# sunclock_back.net
KiCad netlist of a schematic drawn in EAGLE
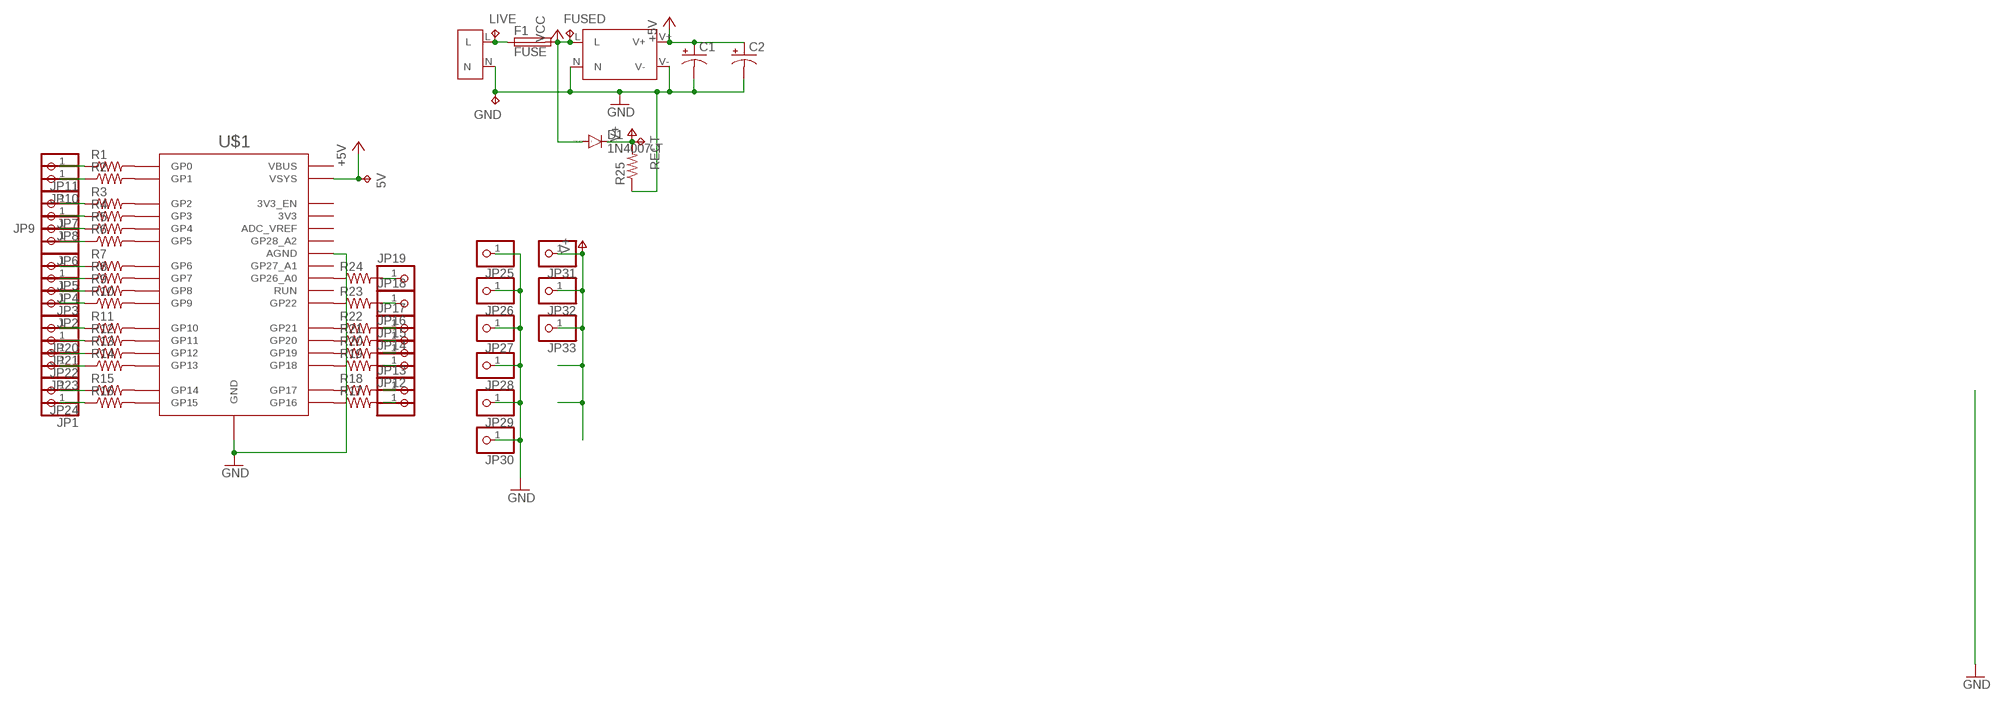
[diagram p0: schematic, sheet 1]

(export (version "E")
  (design (tool "Eeschema 10.0.6"))
  (components
    (comp (ref "5V")
      (value "TPB2,54")
      (footprint "eagle-import:B2,54")
      (libsource (lib "eagle-import") (part "TPB2,54"))
    )
    (comp (ref "AC1")
      (value "AC_IN")
      (footprint "eagle-import:AC_IN")
      (libsource (lib "eagle-import") (part "AC_IN"))
    )
    (comp (ref "C1")
      (value "CPOL-USE3.5-10")
      (footprint "eagle-import:E3,5-10")
      (libsource (lib "eagle-import") (part "CPOL-USE3.5-10"))
    )
    (comp (ref "C2")
      (value "CPOL-USE3.5-10")
      (footprint "eagle-import:E3,5-10")
      (libsource (lib "eagle-import") (part "CPOL-USE3.5-10"))
    )
    (comp (ref "D1")
      (value "1N4007-T")
      (footprint "eagle-import:DIOAD1140W86L463D236B")
      (libsource (lib "eagle-import") (part "1N4007-T"))
    )
    (comp (ref "F1")
      (value "FUSE")
      (footprint "eagle-import:FUSE")
      (libsource (lib "eagle-import") (part "FUSE"))
    )
    (comp (ref "FUSED")
      (value "TPB2,54")
      (footprint "eagle-import:B2,54")
      (libsource (lib "eagle-import") (part "TPB2,54"))
    )
    (comp (ref "GND")
      (value "TPB2,54")
      (footprint "eagle-import:B2,54")
      (libsource (lib "eagle-import") (part "TPB2,54"))
    )
    (comp (ref "JP1")
      (value "PINHD-1X1")
      (footprint "eagle-import:1X01")
      (libsource (lib "eagle-import") (part "PINHD-1X1"))
    )
    (comp (ref "JP2")
      (value "PINHD-1X1")
      (footprint "eagle-import:1X01")
      (libsource (lib "eagle-import") (part "PINHD-1X1"))
    )
    (comp (ref "JP3")
      (value "PINHD-1X1")
      (footprint "eagle-import:1X01")
      (libsource (lib "eagle-import") (part "PINHD-1X1"))
    )
    (comp (ref "JP4")
      (value "PINHD-1X1")
      (footprint "eagle-import:1X01")
      (libsource (lib "eagle-import") (part "PINHD-1X1"))
    )
    (comp (ref "JP5")
      (value "PINHD-1X1")
      (footprint "eagle-import:1X01")
      (libsource (lib "eagle-import") (part "PINHD-1X1"))
    )
    (comp (ref "JP6")
      (value "PINHD-1X1")
      (footprint "eagle-import:1X01")
      (libsource (lib "eagle-import") (part "PINHD-1X1"))
    )
    (comp (ref "JP7")
      (value "PINHD-1X1")
      (footprint "eagle-import:1X01")
      (libsource (lib "eagle-import") (part "PINHD-1X1"))
    )
    (comp (ref "JP8")
      (value "PINHD-1X1")
      (footprint "eagle-import:1X01")
      (libsource (lib "eagle-import") (part "PINHD-1X1"))
    )
    (comp (ref "JP9")
      (value "PINHD-1X1")
      (footprint "eagle-import:1X01")
      (libsource (lib "eagle-import") (part "PINHD-1X1"))
    )
    (comp (ref "JP10")
      (value "PINHD-1X1")
      (footprint "eagle-import:1X01")
      (libsource (lib "eagle-import") (part "PINHD-1X1"))
    )
    (comp (ref "JP11")
      (value "PINHD-1X1")
      (footprint "eagle-import:1X01")
      (libsource (lib "eagle-import") (part "PINHD-1X1"))
    )
    (comp (ref "JP12")
      (value "PINHD-1X1")
      (footprint "eagle-import:1X01")
      (libsource (lib "eagle-import") (part "PINHD-1X1"))
    )
    (comp (ref "JP13")
      (value "PINHD-1X1")
      (footprint "eagle-import:1X01")
      (libsource (lib "eagle-import") (part "PINHD-1X1"))
    )
    (comp (ref "JP14")
      (value "PINHD-1X1")
      (footprint "eagle-import:1X01")
      (libsource (lib "eagle-import") (part "PINHD-1X1"))
    )
    (comp (ref "JP15")
      (value "PINHD-1X1")
      (footprint "eagle-import:1X01")
      (libsource (lib "eagle-import") (part "PINHD-1X1"))
    )
    (comp (ref "JP16")
      (value "PINHD-1X1")
      (footprint "eagle-import:1X01")
      (libsource (lib "eagle-import") (part "PINHD-1X1"))
    )
    (comp (ref "JP17")
      (value "PINHD-1X1")
      (footprint "eagle-import:1X01")
      (libsource (lib "eagle-import") (part "PINHD-1X1"))
    )
    (comp (ref "JP18")
      (value "PINHD-1X1")
      (footprint "eagle-import:1X01")
      (libsource (lib "eagle-import") (part "PINHD-1X1"))
    )
    (comp (ref "JP19")
      (value "PINHD-1X1")
      (footprint "eagle-import:1X01")
      (libsource (lib "eagle-import") (part "PINHD-1X1"))
    )
    (comp (ref "JP20")
      (value "PINHD-1X1")
      (footprint "eagle-import:1X01")
      (libsource (lib "eagle-import") (part "PINHD-1X1"))
    )
    (comp (ref "JP21")
      (value "PINHD-1X1")
      (footprint "eagle-import:1X01")
      (libsource (lib "eagle-import") (part "PINHD-1X1"))
    )
    (comp (ref "JP22")
      (value "PINHD-1X1")
      (footprint "eagle-import:1X01")
      (libsource (lib "eagle-import") (part "PINHD-1X1"))
    )
    (comp (ref "JP23")
      (value "PINHD-1X1")
      (footprint "eagle-import:1X01")
      (libsource (lib "eagle-import") (part "PINHD-1X1"))
    )
    (comp (ref "JP24")
      (value "PINHD-1X1")
      (footprint "eagle-import:1X01")
      (libsource (lib "eagle-import") (part "PINHD-1X1"))
    )
    (comp (ref "JP25")
      (value "PINHD-1X1")
      (footprint "eagle-import:1X01")
      (libsource (lib "eagle-import") (part "PINHD-1X1"))
    )
    (comp (ref "JP26")
      (value "PINHD-1X1")
      (footprint "eagle-import:1X01")
      (libsource (lib "eagle-import") (part "PINHD-1X1"))
    )
    (comp (ref "JP27")
      (value "PINHD-1X1")
      (footprint "eagle-import:1X01")
      (libsource (lib "eagle-import") (part "PINHD-1X1"))
    )
    (comp (ref "JP28")
      (value "PINHD-1X1")
      (footprint "eagle-import:1X01")
      (libsource (lib "eagle-import") (part "PINHD-1X1"))
    )
    (comp (ref "JP29")
      (value "PINHD-1X1")
      (footprint "eagle-import:1X01")
      (libsource (lib "eagle-import") (part "PINHD-1X1"))
    )
    (comp (ref "JP30")
      (value "PINHD-1X1")
      (footprint "eagle-import:1X01")
      (libsource (lib "eagle-import") (part "PINHD-1X1"))
    )
    (comp (ref "JP31")
      (value "PINHD-1X1")
      (footprint "eagle-import:1X01")
      (libsource (lib "eagle-import") (part "PINHD-1X1"))
    )
    (comp (ref "JP32")
      (value "PINHD-1X1")
      (footprint "eagle-import:1X01")
      (libsource (lib "eagle-import") (part "PINHD-1X1"))
    )
    (comp (ref "JP33")
      (value "PINHD-1X1")
      (footprint "eagle-import:1X01")
      (libsource (lib "eagle-import") (part "PINHD-1X1"))
    )
    (comp (ref "LIVE")
      (value "TPB2,54")
      (footprint "eagle-import:B2,54")
      (libsource (lib "eagle-import") (part "TPB2,54"))
    )
    (comp (ref "P1")
      (value "ACDC")
      (footprint "eagle-import:ACDC")
      (libsource (lib "eagle-import") (part "ACDC"))
    )
    (comp (ref "R1")
      (value "R-US_0204/7")
      (footprint "eagle-import:0204_7")
      (libsource (lib "eagle-import") (part "R-US_0204/7"))
    )
    (comp (ref "R2")
      (value "R-US_0204/7")
      (footprint "eagle-import:0204_7")
      (libsource (lib "eagle-import") (part "R-US_0204/7"))
    )
    (comp (ref "R3")
      (value "R-US_0204/7")
      (footprint "eagle-import:0204_7")
      (libsource (lib "eagle-import") (part "R-US_0204/7"))
    )
    (comp (ref "R4")
      (value "R-US_0204/7")
      (footprint "eagle-import:0204_7")
      (libsource (lib "eagle-import") (part "R-US_0204/7"))
    )
    (comp (ref "R5")
      (value "R-US_0204/7")
      (footprint "eagle-import:0204_7")
      (libsource (lib "eagle-import") (part "R-US_0204/7"))
    )
    (comp (ref "R6")
      (value "R-US_0204/7")
      (footprint "eagle-import:0204_7")
      (libsource (lib "eagle-import") (part "R-US_0204/7"))
    )
    (comp (ref "R7")
      (value "R-US_0204/7")
      (footprint "eagle-import:0204_7")
      (libsource (lib "eagle-import") (part "R-US_0204/7"))
    )
    (comp (ref "R8")
      (value "R-US_0204/7")
      (footprint "eagle-import:0204_7")
      (libsource (lib "eagle-import") (part "R-US_0204/7"))
    )
    (comp (ref "R9")
      (value "R-US_0204/7")
      (footprint "eagle-import:0204_7")
      (libsource (lib "eagle-import") (part "R-US_0204/7"))
    )
    (comp (ref "R10")
      (value "R-US_0204/7")
      (footprint "eagle-import:0204_7")
      (libsource (lib "eagle-import") (part "R-US_0204/7"))
    )
    (comp (ref "R11")
      (value "R-US_0204/7")
      (footprint "eagle-import:0204_7")
      (libsource (lib "eagle-import") (part "R-US_0204/7"))
    )
    (comp (ref "R12")
      (value "R-US_0204/7")
      (footprint "eagle-import:0204_7")
      (libsource (lib "eagle-import") (part "R-US_0204/7"))
    )
    (comp (ref "R13")
      (value "R-US_0204/7")
      (footprint "eagle-import:0204_7")
      (libsource (lib "eagle-import") (part "R-US_0204/7"))
    )
    (comp (ref "R14")
      (value "R-US_0204/7")
      (footprint "eagle-import:0204_7")
      (libsource (lib "eagle-import") (part "R-US_0204/7"))
    )
    (comp (ref "R15")
      (value "R-US_0204/7")
      (footprint "eagle-import:0204_7")
      (libsource (lib "eagle-import") (part "R-US_0204/7"))
    )
    (comp (ref "R16")
      (value "R-US_0204/7")
      (footprint "eagle-import:0204_7")
      (libsource (lib "eagle-import") (part "R-US_0204/7"))
    )
    (comp (ref "R17")
      (value "R-US_0204/7")
      (footprint "eagle-import:0204_7")
      (libsource (lib "eagle-import") (part "R-US_0204/7"))
    )
    (comp (ref "R18")
      (value "R-US_0204/7")
      (footprint "eagle-import:0204_7")
      (libsource (lib "eagle-import") (part "R-US_0204/7"))
    )
    (comp (ref "R19")
      (value "R-US_0204/7")
      (footprint "eagle-import:0204_7")
      (libsource (lib "eagle-import") (part "R-US_0204/7"))
    )
    (comp (ref "R20")
      (value "R-US_0204/7")
      (footprint "eagle-import:0204_7")
      (libsource (lib "eagle-import") (part "R-US_0204/7"))
    )
    (comp (ref "R21")
      (value "R-US_0204/7")
      (footprint "eagle-import:0204_7")
      (libsource (lib "eagle-import") (part "R-US_0204/7"))
    )
    (comp (ref "R22")
      (value "R-US_0204/7")
      (footprint "eagle-import:0204_7")
      (libsource (lib "eagle-import") (part "R-US_0204/7"))
    )
    (comp (ref "R23")
      (value "R-US_0204/7")
      (footprint "eagle-import:0204_7")
      (libsource (lib "eagle-import") (part "R-US_0204/7"))
    )
    (comp (ref "R24")
      (value "R-US_0204/7")
      (footprint "eagle-import:0204_7")
      (libsource (lib "eagle-import") (part "R-US_0204/7"))
    )
    (comp (ref "R25")
      (value "R-US_0204/7")
      (footprint "eagle-import:0204_7")
      (libsource (lib "eagle-import") (part "R-US_0204/7"))
    )
    (comp (ref "RECT")
      (value "TPB2,54")
      (footprint "eagle-import:B2,54")
      (libsource (lib "eagle-import") (part "TPB2,54"))
    )
    (comp (ref "U$1")
      (value "RPI_PICO-TH")
      (footprint "eagle-import:RPI_PICO_TH")
      (libsource (lib "eagle-import") (part "RPI_PICO-TH"))
    )
  )
  (nets
    (net (code "1") (name "+5V") (class "Default")
      (node (ref "5V") (pin "TP") (pinfunction "TP_TP") (pintype "input"))
      (node (ref "C1") (pin "+") (pinfunction "+_+") (pintype "passive"))
      (node (ref "C2") (pin "+") (pinfunction "+_+") (pintype "passive"))
      (node (ref "P1") (pin "V+") (pinfunction "V+_V+") (pintype "bidirectional"))
      (node (ref "U$1") (pin "VSYS") (pinfunction "VSYS_VSYS") (pintype "bidirectional"))
    )
    (net (code "2") (name "GND") (class "Default")
      (node (ref "AC1") (pin "N") (pinfunction "N_N") (pintype "bidirectional"))
      (node (ref "C1") (pin "-") (pinfunction "-_-") (pintype "passive"))
      (node (ref "C2") (pin "-") (pinfunction "-_-") (pintype "passive"))
      (node (ref "GND") (pin "TP") (pinfunction "TP_TP") (pintype "input"))
      (node (ref "JP25") (pin "1") (pinfunction "1_1") (pintype "passive"))
      (node (ref "JP26") (pin "1") (pinfunction "1_1") (pintype "passive"))
      (node (ref "JP27") (pin "1") (pinfunction "1_1") (pintype "passive"))
      (node (ref "JP28") (pin "1") (pinfunction "1_1") (pintype "passive"))
      (node (ref "JP29") (pin "1") (pinfunction "1_1") (pintype "passive"))
      (node (ref "JP30") (pin "1") (pinfunction "1_1") (pintype "passive"))
      (node (ref "P1") (pin "N") (pinfunction "N_N") (pintype "bidirectional"))
      (node (ref "P1") (pin "V-") (pinfunction "V-_V-") (pintype "bidirectional"))
      (node (ref "R25") (pin "1") (pinfunction "1_1") (pintype "passive"))
      (node (ref "U$1") (pin "AGND") (pinfunction "AGND_AGND") (pintype "bidirectional"))
      (node (ref "U$1") (pin "GND@1") (pinfunction "GND_GND@1") (pintype "bidirectional"))
      (node (ref "U$1") (pin "GND@2") (pinfunction "GND_GND@2") (pintype "bidirectional"))
      (node (ref "U$1") (pin "GND@3") (pinfunction "GND_GND@3") (pintype "bidirectional"))
      (node (ref "U$1") (pin "GND@4") (pinfunction "GND_GND@4") (pintype "bidirectional"))
      (node (ref "U$1") (pin "GND@6") (pinfunction "GND_GND@6") (pintype "bidirectional"))
      (node (ref "U$1") (pin "GND@7") (pinfunction "GND_GND@7") (pintype "bidirectional"))
      (node (ref "U$1") (pin "GND@8") (pinfunction "GND_GND@8") (pintype "bidirectional"))
    )
    (net (code "3") (name "Net-(F1-1)") (class "Default")
      (node (ref "AC1") (pin "L") (pinfunction "L_L") (pintype "bidirectional"))
      (node (ref "F1") (pin "P$1") (pinfunction "1_P$1") (pintype "passive"))
      (node (ref "LIVE") (pin "TP") (pinfunction "TP_TP") (pintype "input"))
    )
    (net (code "4") (name "Net-(JP1-Pad1)") (class "Default")
      (node (ref "JP1") (pin "1") (pinfunction "1_1") (pintype "passive"))
      (node (ref "R16") (pin "1") (pinfunction "1_1") (pintype "passive"))
    )
    (net (code "5") (name "Net-(JP2-Pad1)") (class "Default")
      (node (ref "JP2") (pin "1") (pinfunction "1_1") (pintype "passive"))
      (node (ref "R10") (pin "1") (pinfunction "1_1") (pintype "passive"))
    )
    (net (code "6") (name "Net-(JP3-Pad1)") (class "Default")
      (node (ref "JP3") (pin "1") (pinfunction "1_1") (pintype "passive"))
      (node (ref "R9") (pin "1") (pinfunction "1_1") (pintype "passive"))
    )
    (net (code "7") (name "Net-(JP4-Pad1)") (class "Default")
      (node (ref "JP4") (pin "1") (pinfunction "1_1") (pintype "passive"))
      (node (ref "R8") (pin "1") (pinfunction "1_1") (pintype "passive"))
    )
    (net (code "8") (name "Net-(JP5-Pad1)") (class "Default")
      (node (ref "JP5") (pin "1") (pinfunction "1_1") (pintype "passive"))
      (node (ref "R7") (pin "1") (pinfunction "1_1") (pintype "passive"))
    )
    (net (code "9") (name "Net-(JP6-Pad1)") (class "Default")
      (node (ref "JP6") (pin "1") (pinfunction "1_1") (pintype "passive"))
      (node (ref "R6") (pin "1") (pinfunction "1_1") (pintype "passive"))
    )
    (net (code "10") (name "Net-(JP7-Pad1)") (class "Default")
      (node (ref "JP7") (pin "1") (pinfunction "1_1") (pintype "passive"))
      (node (ref "R3") (pin "1") (pinfunction "1_1") (pintype "passive"))
    )
    (net (code "11") (name "Net-(JP8-Pad1)") (class "Default")
      (node (ref "JP8") (pin "1") (pinfunction "1_1") (pintype "passive"))
      (node (ref "R4") (pin "1") (pinfunction "1_1") (pintype "passive"))
    )
    (net (code "12") (name "Net-(JP9-Pad1)") (class "Default")
      (node (ref "JP9") (pin "1") (pinfunction "1_1") (pintype "passive"))
      (node (ref "R5") (pin "1") (pinfunction "1_1") (pintype "passive"))
    )
    (net (code "13") (name "Net-(JP10-Pad1)") (class "Default")
      (node (ref "JP10") (pin "1") (pinfunction "1_1") (pintype "passive"))
      (node (ref "R2") (pin "1") (pinfunction "1_1") (pintype "passive"))
    )
    (net (code "14") (name "Net-(JP11-Pad1)") (class "Default")
      (node (ref "JP11") (pin "1") (pinfunction "1_1") (pintype "passive"))
      (node (ref "R1") (pin "1") (pinfunction "1_1") (pintype "passive"))
    )
    (net (code "15") (name "Net-(JP12-Pad1)") (class "Default")
      (node (ref "JP12") (pin "1") (pinfunction "1_1") (pintype "passive"))
      (node (ref "R17") (pin "2") (pinfunction "2_2") (pintype "passive"))
    )
    (net (code "16") (name "Net-(JP13-Pad1)") (class "Default")
      (node (ref "JP13") (pin "1") (pinfunction "1_1") (pintype "passive"))
      (node (ref "R18") (pin "2") (pinfunction "2_2") (pintype "passive"))
    )
    (net (code "17") (name "Net-(JP14-Pad1)") (class "Default")
      (node (ref "JP14") (pin "1") (pinfunction "1_1") (pintype "passive"))
      (node (ref "R19") (pin "2") (pinfunction "2_2") (pintype "passive"))
    )
    (net (code "18") (name "Net-(JP15-Pad1)") (class "Default")
      (node (ref "JP15") (pin "1") (pinfunction "1_1") (pintype "passive"))
      (node (ref "R20") (pin "2") (pinfunction "2_2") (pintype "passive"))
    )
    (net (code "19") (name "Net-(JP16-Pad1)") (class "Default")
      (node (ref "JP16") (pin "1") (pinfunction "1_1") (pintype "passive"))
      (node (ref "R21") (pin "2") (pinfunction "2_2") (pintype "passive"))
    )
    (net (code "20") (name "Net-(JP17-Pad1)") (class "Default")
      (node (ref "JP17") (pin "1") (pinfunction "1_1") (pintype "passive"))
      (node (ref "R22") (pin "2") (pinfunction "2_2") (pintype "passive"))
    )
    (net (code "21") (name "Net-(JP18-Pad1)") (class "Default")
      (node (ref "JP18") (pin "1") (pinfunction "1_1") (pintype "passive"))
      (node (ref "R23") (pin "2") (pinfunction "2_2") (pintype "passive"))
    )
    (net (code "22") (name "Net-(JP19-Pad1)") (class "Default")
      (node (ref "JP19") (pin "1") (pinfunction "1_1") (pintype "passive"))
      (node (ref "R24") (pin "2") (pinfunction "2_2") (pintype "passive"))
    )
    (net (code "23") (name "Net-(JP20-Pad1)") (class "Default")
      (node (ref "JP20") (pin "1") (pinfunction "1_1") (pintype "passive"))
      (node (ref "R11") (pin "1") (pinfunction "1_1") (pintype "passive"))
    )
    (net (code "24") (name "Net-(JP21-Pad1)") (class "Default")
      (node (ref "JP21") (pin "1") (pinfunction "1_1") (pintype "passive"))
      (node (ref "R12") (pin "1") (pinfunction "1_1") (pintype "passive"))
    )
    (net (code "25") (name "Net-(JP22-Pad1)") (class "Default")
      (node (ref "JP22") (pin "1") (pinfunction "1_1") (pintype "passive"))
      (node (ref "R13") (pin "1") (pinfunction "1_1") (pintype "passive"))
    )
    (net (code "26") (name "Net-(JP23-Pad1)") (class "Default")
      (node (ref "JP23") (pin "1") (pinfunction "1_1") (pintype "passive"))
      (node (ref "R14") (pin "1") (pinfunction "1_1") (pintype "passive"))
    )
    (net (code "27") (name "Net-(JP24-Pad1)") (class "Default")
      (node (ref "JP24") (pin "1") (pinfunction "1_1") (pintype "passive"))
      (node (ref "R15") (pin "1") (pinfunction "1_1") (pintype "passive"))
    )
    (net (code "28") (name "Net-(R1-Pad2)") (class "Default")
      (node (ref "R1") (pin "2") (pinfunction "2_2") (pintype "passive"))
      (node (ref "U$1") (pin "GP0") (pinfunction "GP0_GP0") (pintype "bidirectional"))
    )
    (net (code "29") (name "Net-(R2-Pad2)") (class "Default")
      (node (ref "R2") (pin "2") (pinfunction "2_2") (pintype "passive"))
      (node (ref "U$1") (pin "GP1") (pinfunction "GP1_GP1") (pintype "bidirectional"))
    )
    (net (code "30") (name "Net-(R3-Pad2)") (class "Default")
      (node (ref "R3") (pin "2") (pinfunction "2_2") (pintype "passive"))
      (node (ref "U$1") (pin "GP2") (pinfunction "GP2_GP2") (pintype "bidirectional"))
    )
    (net (code "31") (name "Net-(R4-Pad2)") (class "Default")
      (node (ref "R4") (pin "2") (pinfunction "2_2") (pintype "passive"))
      (node (ref "U$1") (pin "GP3") (pinfunction "GP3_GP3") (pintype "bidirectional"))
    )
    (net (code "32") (name "Net-(R5-Pad2)") (class "Default")
      (node (ref "R5") (pin "2") (pinfunction "2_2") (pintype "passive"))
      (node (ref "U$1") (pin "GP4") (pinfunction "GP4_GP4") (pintype "bidirectional"))
    )
    (net (code "33") (name "Net-(R6-Pad2)") (class "Default")
      (node (ref "R6") (pin "2") (pinfunction "2_2") (pintype "passive"))
      (node (ref "U$1") (pin "GP5") (pinfunction "GP5_GP5") (pintype "bidirectional"))
    )
    (net (code "34") (name "Net-(R7-Pad2)") (class "Default")
      (node (ref "R7") (pin "2") (pinfunction "2_2") (pintype "passive"))
      (node (ref "U$1") (pin "GP6") (pinfunction "GP6_GP6") (pintype "bidirectional"))
    )
    (net (code "35") (name "Net-(R8-Pad2)") (class "Default")
      (node (ref "R8") (pin "2") (pinfunction "2_2") (pintype "passive"))
      (node (ref "U$1") (pin "GP7") (pinfunction "GP7_GP7") (pintype "bidirectional"))
    )
    (net (code "36") (name "Net-(R9-Pad2)") (class "Default")
      (node (ref "R9") (pin "2") (pinfunction "2_2") (pintype "passive"))
      (node (ref "U$1") (pin "GP8") (pinfunction "GP8_GP8") (pintype "bidirectional"))
    )
    (net (code "37") (name "Net-(R10-Pad2)") (class "Default")
      (node (ref "R10") (pin "2") (pinfunction "2_2") (pintype "passive"))
      (node (ref "U$1") (pin "GP9") (pinfunction "GP9_GP9") (pintype "bidirectional"))
    )
    (net (code "38") (name "Net-(R11-Pad2)") (class "Default")
      (node (ref "R11") (pin "2") (pinfunction "2_2") (pintype "passive"))
      (node (ref "U$1") (pin "GP10") (pinfunction "GP10_GP10") (pintype "bidirectional"))
    )
    (net (code "39") (name "Net-(R12-Pad2)") (class "Default")
      (node (ref "R12") (pin "2") (pinfunction "2_2") (pintype "passive"))
      (node (ref "U$1") (pin "GP11") (pinfunction "GP11_GP11") (pintype "bidirectional"))
    )
    (net (code "40") (name "Net-(R13-Pad2)") (class "Default")
      (node (ref "R13") (pin "2") (pinfunction "2_2") (pintype "passive"))
      (node (ref "U$1") (pin "GP12") (pinfunction "GP12_GP12") (pintype "bidirectional"))
    )
    (net (code "41") (name "Net-(R14-Pad2)") (class "Default")
      (node (ref "R14") (pin "2") (pinfunction "2_2") (pintype "passive"))
      (node (ref "U$1") (pin "GP13") (pinfunction "GP13_GP13") (pintype "bidirectional"))
    )
    (net (code "42") (name "Net-(R15-Pad2)") (class "Default")
      (node (ref "R15") (pin "2") (pinfunction "2_2") (pintype "passive"))
      (node (ref "U$1") (pin "GP14") (pinfunction "GP14_GP14") (pintype "bidirectional"))
    )
    (net (code "43") (name "Net-(R16-Pad2)") (class "Default")
      (node (ref "R16") (pin "2") (pinfunction "2_2") (pintype "passive"))
      (node (ref "U$1") (pin "GP15") (pinfunction "GP15_GP15") (pintype "bidirectional"))
    )
    (net (code "44") (name "Net-(R17-Pad1)") (class "Default")
      (node (ref "R17") (pin "1") (pinfunction "1_1") (pintype "passive"))
      (node (ref "U$1") (pin "GP16") (pinfunction "GP16_GP16") (pintype "bidirectional"))
    )
    (net (code "45") (name "Net-(R18-Pad1)") (class "Default")
      (node (ref "R18") (pin "1") (pinfunction "1_1") (pintype "passive"))
      (node (ref "U$1") (pin "GP17") (pinfunction "GP17_GP17") (pintype "bidirectional"))
    )
    (net (code "46") (name "Net-(R19-Pad1)") (class "Default")
      (node (ref "R19") (pin "1") (pinfunction "1_1") (pintype "passive"))
      (node (ref "U$1") (pin "GP18") (pinfunction "GP18_GP18") (pintype "bidirectional"))
    )
    (net (code "47") (name "Net-(R20-Pad1)") (class "Default")
      (node (ref "R20") (pin "1") (pinfunction "1_1") (pintype "passive"))
      (node (ref "U$1") (pin "GP19") (pinfunction "GP19_GP19") (pintype "bidirectional"))
    )
    (net (code "48") (name "Net-(R21-Pad1)") (class "Default")
      (node (ref "R21") (pin "1") (pinfunction "1_1") (pintype "passive"))
      (node (ref "U$1") (pin "GP20") (pinfunction "GP20_GP20") (pintype "bidirectional"))
    )
    (net (code "49") (name "Net-(R22-Pad1)") (class "Default")
      (node (ref "R22") (pin "1") (pinfunction "1_1") (pintype "passive"))
      (node (ref "U$1") (pin "GP21") (pinfunction "GP21_GP21") (pintype "bidirectional"))
    )
    (net (code "50") (name "Net-(R23-Pad1)") (class "Default")
      (node (ref "R23") (pin "1") (pinfunction "1_1") (pintype "passive"))
      (node (ref "U$1") (pin "GP22") (pinfunction "GP22_GP22") (pintype "bidirectional"))
    )
    (net (code "51") (name "Net-(R24-Pad1)") (class "Default")
      (node (ref "R24") (pin "1") (pinfunction "1_1") (pintype "passive"))
      (node (ref "U$1") (pin "GP26_A0") (pinfunction "GP26_A0_GP26_A0") (pintype "bidirectional"))
    )
    (net (code "52") (name "V+") (class "Default")
      (node (ref "D1") (pin "1") (pinfunction "C_1") (pintype "passive"))
      (node (ref "JP31") (pin "1") (pinfunction "1_1") (pintype "passive"))
      (node (ref "JP32") (pin "1") (pinfunction "1_1") (pintype "passive"))
      (node (ref "JP33") (pin "1") (pinfunction "1_1") (pintype "passive"))
      (node (ref "R25") (pin "2") (pinfunction "2_2") (pintype "passive"))
      (node (ref "RECT") (pin "TP") (pinfunction "TP_TP") (pintype "input"))
    )
    (net (code "53") (name "VCC") (class "Default")
      (node (ref "D1") (pin "2") (pinfunction "A_2") (pintype "passive"))
      (node (ref "F1") (pin "P$2") (pinfunction "2_P$2") (pintype "passive"))
      (node (ref "FUSED") (pin "TP") (pinfunction "TP_TP") (pintype "input"))
      (node (ref "P1") (pin "L") (pinfunction "L_L") (pintype "bidirectional"))
    )
    (net (code "54") (name "unconnected-(U$1-Pad3V3)") (class "Default")
      (node (ref "U$1") (pin "3V3") (pinfunction "3V3_3V3") (pintype "bidirectional"))
    )
    (net (code "55") (name "unconnected-(U$1-Pad3V3_EN)") (class "Default")
      (node (ref "U$1") (pin "3V3_EN") (pinfunction "3V3_EN_3V3_EN") (pintype "bidirectional"))
    )
    (net (code "56") (name "unconnected-(U$1-PadADC_VREF)") (class "Default")
      (node (ref "U$1") (pin "ADC_VREF") (pinfunction "ADC_VREF_ADC_VREF") (pintype "bidirectional"))
    )
    (net (code "57") (name "unconnected-(U$1-PadGP27_A1)") (class "Default")
      (node (ref "U$1") (pin "GP27_A1") (pinfunction "GP27_A1_GP27_A1") (pintype "bidirectional"))
    )
    (net (code "58") (name "unconnected-(U$1-PadGP28_A2)") (class "Default")
      (node (ref "U$1") (pin "GP28_A2") (pinfunction "GP28_A2_GP28_A2") (pintype "bidirectional"))
    )
    (net (code "59") (name "unconnected-(U$1-PadRUN)") (class "Default")
      (node (ref "U$1") (pin "RUN") (pinfunction "RUN_RUN") (pintype "bidirectional"))
    )
    (net (code "60") (name "unconnected-(U$1-PadVBUS)") (class "Default")
      (node (ref "U$1") (pin "VBUS") (pinfunction "VBUS_VBUS") (pintype "bidirectional"))
    )
  )
)
